# 04_Motors.net
KiCad netlist of a schematic drawn in Altium Designer
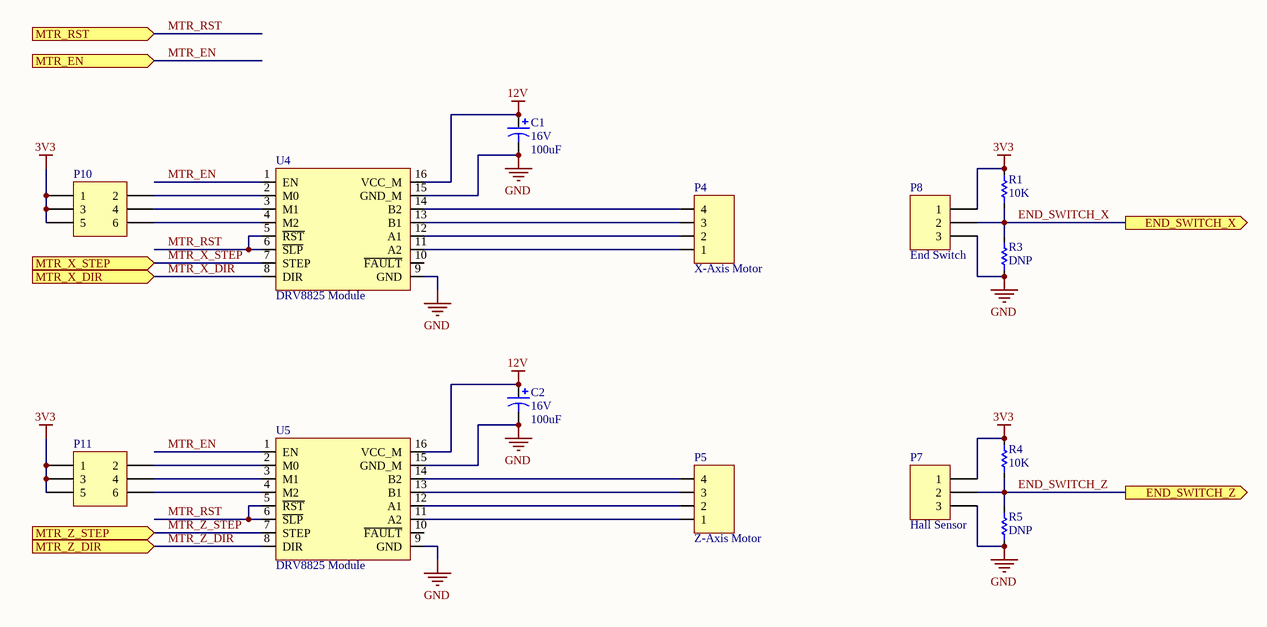
[diagram p0: 04_Motors.SchDoc]

(export (version "E")
  (design (tool "Eeschema 10.0.6"))
  (components
    (comp (ref "C1")
      (value "16V")
      (footprint "Moji Footprintovi:Electrolytic Cap 3.2mm")
      (description "Polarized Capacitor (Axial)")
      (fields
        (field (name "MANUFACTURER") "Würth Elektronik")
        (field (name "MANUFACTURER PART NUMBER") "870135675003")
        (field (name "ALTIUM_VALUE") "100uF")
      )
      (libsource (lib "Schematic_Misc") (part "Cap Electrolytic"))
    )
    (comp (ref "C2")
      (value "16V")
      (footprint "Moji Footprintovi:Electrolytic Cap 3.2mm")
      (description "Polarized Capacitor (Axial)")
      (fields
        (field (name "MANUFACTURER") "Würth Elektronik")
        (field (name "MANUFACTURER PART NUMBER") "870135675003")
        (field (name "ALTIUM_VALUE") "100uF")
      )
      (libsource (lib "Schematic_Misc") (part "Cap Electrolytic"))
    )
    (comp (ref "P4")
      (value "X-Axis Motor")
      (footprint "Footprint_Misc:TERMINAL_4POS_90DEG_2PART")
      (description "TERM BLOCK HDR 4POS 90DEG 3.5MM")
      (fields
        (field (name "DISTRIBUTOR PART NUMBER") "732-2771-ND")
        (field (name "MANUFACTURER") "Würth Elektronik")
      )
      (libsource (lib "Schematic_Misc") (part "Terminal 4_691322110004"))
    )
    (comp (ref "P5")
      (value "Z-Axis Motor")
      (footprint "Footprint_Misc:TERMINAL_4POS_90DEG_2PART")
      (description "TERM BLOCK HDR 4POS 90DEG 3.5MM")
      (fields
        (field (name "DISTRIBUTOR PART NUMBER") "732-2771-ND")
        (field (name "MANUFACTURER") "Würth Elektronik")
      )
      (libsource (lib "Schematic_Misc") (part "Terminal 4_691322110004"))
    )
    (comp (ref "P7")
      (value "Hall Sensor")
      (footprint "Footprint_Misc:TERMINAL_3POS_90DEG_2PART")
      (description "TERM BLOCK HDR 3POS 90DEG 3.5MM")
      (fields
        (field (name "MANUFACTURER") "Würth Elektronik")
        (field (name "MANUFACTURER PART NUMBER") "691322110003")
      )
      (libsource (lib "Schematic_Misc") (part "Terminal 3_691322110003_1"))
    )
    (comp (ref "P8")
      (value "End Switch")
      (footprint "Footprint_Misc:TERMINAL_3POS_90DEG_2PART")
      (description "TERM BLOCK HDR 3POS 90DEG 3.5MM")
      (fields
        (field (name "MANUFACTURER") "Würth Elektronik")
        (field (name "MANUFACTURER PART NUMBER") "691322110003")
      )
      (libsource (lib "Schematic_Misc") (part "Terminal 3_691322110003_1"))
    )
    (comp (ref "P10")
      (value "Header 3X2")
      (footprint "HDR2X3")
      (description "Header, 3-Pin, Dual row")
      (fields (field (name "DISTRIBUTOR PART NUMBER") "WM13106-ND") (field (name "MANUFACTURER") "Molex"))
      (libsource (lib "Miscellaneous Connectors") (part "Header 3X2"))
    )
    (comp (ref "P11")
      (value "Header 3X2")
      (footprint "HDR2X3")
      (description "Header, 3-Pin, Dual row")
      (fields (field (name "DISTRIBUTOR PART NUMBER") "WM13106-ND") (field (name "MANUFACTURER") "Molex"))
      (libsource (lib "Miscellaneous Connectors") (part "Header 3X2"))
    )
    (comp (ref "R1")
      (value "10K")
      (footprint "Moji Footprintovi:0603")
      (description "Resistor")
      (fields
        (field (name "DISTRIBUTOR PART NUMBER") "13-AA0603FR-0710KLCT-ND")
        (field (name "MANUFACTURER") "YAGEO")
      )
      (libsource (lib "Schematic_Misc") (part "Res"))
    )
    (comp (ref "R3")
      (value "DNP")
      (footprint "Moji Footprintovi:0603")
      (description "Resistor")
      (fields
        (field (name "DISTRIBUTOR PART NUMBER") "13-AA0603FR-0710KLCT-ND")
        (field (name "MANUFACTURER") "YAGEO")
      )
      (libsource (lib "Schematic_Misc") (part "Res"))
    )
    (comp (ref "R4")
      (value "10K")
      (footprint "Moji Footprintovi:0603")
      (description "Resistor")
      (fields
        (field (name "DISTRIBUTOR PART NUMBER") "13-AA0603FR-0710KLCT-ND")
        (field (name "MANUFACTURER") "YAGEO")
      )
      (libsource (lib "Schematic_Misc") (part "Res"))
    )
    (comp (ref "R5")
      (value "DNP")
      (footprint "Moji Footprintovi:0603")
      (description "Resistor")
      (fields
        (field (name "DISTRIBUTOR PART NUMBER") "13-AA0603FR-0710KLCT-ND")
        (field (name "MANUFACTURER") "YAGEO")
      )
      (libsource (lib "Schematic_Misc") (part "Res"))
    )
    (comp (ref "U4")
      (value "DRV8825 Module")
      (footprint "Footprint_Misc:DRV8825_Module")
      (fields (field (name "DISTRIBUTOR PART NUMBER") "https://www.aliexpress.com/item/32597532420.html"))
      (libsource (lib "Schematic_Misc") (part "DRV8825 Module"))
    )
    (comp (ref "U5")
      (value "DRV8825 Module")
      (footprint "Footprint_Misc:DRV8825_Module")
      (fields (field (name "DISTRIBUTOR PART NUMBER") "https://www.aliexpress.com/item/32597532420.html"))
      (libsource (lib "Schematic_Misc") (part "DRV8825 Module"))
    )
  )
  (nets
    (net (code "1") (name "/END_SWITCH_X") (class "Default")
      (node (ref "P8") (pin "2") (pinfunction "2_2") (pintype "passive"))
      (node (ref "R1") (pin "1") (pinfunction "1_1") (pintype "passive"))
      (node (ref "R3") (pin "2") (pinfunction "2_2") (pintype "passive"))
    )
    (net (code "2") (name "/END_SWITCH_Z") (class "Default")
      (node (ref "P7") (pin "2") (pinfunction "2_2") (pintype "passive"))
      (node (ref "R4") (pin "1") (pinfunction "1_1") (pintype "passive"))
      (node (ref "R5") (pin "2") (pinfunction "2_2") (pintype "passive"))
    )
    (net (code "3") (name "/MTR_EN") (class "Default")
      (node (ref "U4") (pin "1") (pinfunction "EN_1") (pintype "passive"))
      (node (ref "U5") (pin "1") (pinfunction "EN_1") (pintype "passive"))
    )
    (net (code "4") (name "/MTR_RST") (class "Default")
      (node (ref "U4") (pin "5") (pinfunction "~{RST}_5") (pintype "passive"))
      (node (ref "U4") (pin "6") (pinfunction "~{SLP}_6") (pintype "passive"))
      (node (ref "U5") (pin "5") (pinfunction "~{RST}_5") (pintype "passive"))
      (node (ref "U5") (pin "6") (pinfunction "~{SLP}_6") (pintype "passive"))
    )
    (net (code "5") (name "/MTR_X_DIR") (class "Default")
      (node (ref "U4") (pin "8") (pinfunction "DIR_8") (pintype "passive"))
    )
    (net (code "6") (name "/MTR_X_STEP") (class "Default")
      (node (ref "U4") (pin "7") (pinfunction "STEP_7") (pintype "passive"))
    )
    (net (code "7") (name "/MTR_Z_DIR") (class "Default")
      (node (ref "U5") (pin "8") (pinfunction "DIR_8") (pintype "passive"))
    )
    (net (code "8") (name "/MTR_Z_STEP") (class "Default")
      (node (ref "U5") (pin "7") (pinfunction "STEP_7") (pintype "passive"))
    )
    (net (code "9") (name "3V3") (class "Default")
      (node (ref "P10") (pin "1") (pinfunction "1_1") (pintype "passive"))
      (node (ref "P10") (pin "3") (pinfunction "3_3") (pintype "passive"))
      (node (ref "P10") (pin "5") (pinfunction "5_5") (pintype "passive"))
      (node (ref "P11") (pin "1") (pinfunction "1_1") (pintype "passive"))
      (node (ref "P11") (pin "3") (pinfunction "3_3") (pintype "passive"))
      (node (ref "P11") (pin "5") (pinfunction "5_5") (pintype "passive"))
      (node (ref "P7") (pin "1") (pinfunction "1_1") (pintype "passive"))
      (node (ref "P8") (pin "1") (pinfunction "1_1") (pintype "passive"))
      (node (ref "R1") (pin "2") (pinfunction "2_2") (pintype "passive"))
      (node (ref "R4") (pin "2") (pinfunction "2_2") (pintype "passive"))
    )
    (net (code "10") (name "12V") (class "Default")
      (node (ref "C1") (pin "1") (pinfunction "1_1") (pintype "passive"))
      (node (ref "C2") (pin "1") (pinfunction "1_1") (pintype "passive"))
      (node (ref "U4") (pin "16") (pinfunction "VCC_M_16") (pintype "passive"))
      (node (ref "U5") (pin "16") (pinfunction "VCC_M_16") (pintype "passive"))
    )
    (net (code "11") (name "GND") (class "Default")
      (node (ref "C1") (pin "2") (pinfunction "2_2") (pintype "passive"))
      (node (ref "C2") (pin "2") (pinfunction "2_2") (pintype "passive"))
      (node (ref "P7") (pin "3") (pinfunction "3_3") (pintype "passive"))
      (node (ref "P8") (pin "3") (pinfunction "3_3") (pintype "passive"))
      (node (ref "R3") (pin "1") (pinfunction "1_1") (pintype "passive"))
      (node (ref "R5") (pin "1") (pinfunction "1_1") (pintype "passive"))
      (node (ref "U4") (pin "15") (pinfunction "GND_M_15") (pintype "passive"))
      (node (ref "U4") (pin "9") (pinfunction "GND_9") (pintype "passive"))
      (node (ref "U5") (pin "15") (pinfunction "GND_M_15") (pintype "passive"))
      (node (ref "U5") (pin "9") (pinfunction "GND_9") (pintype "passive"))
    )
    (net (code "12") (name "Net-(U4-A1)") (class "Default")
      (node (ref "P4") (pin "2") (pinfunction "2_2") (pintype "passive"))
      (node (ref "U4") (pin "12") (pinfunction "A1_12") (pintype "passive"))
    )
    (net (code "13") (name "Net-(U4-A2)") (class "Default")
      (node (ref "P4") (pin "1") (pinfunction "1_1") (pintype "passive"))
      (node (ref "U4") (pin "11") (pinfunction "A2_11") (pintype "passive"))
    )
    (net (code "14") (name "Net-(U4-B1)") (class "Default")
      (node (ref "P4") (pin "3") (pinfunction "3_3") (pintype "passive"))
      (node (ref "U4") (pin "13") (pinfunction "B1_13") (pintype "passive"))
    )
    (net (code "15") (name "Net-(U4-B2)") (class "Default")
      (node (ref "P4") (pin "4") (pinfunction "4_4") (pintype "passive"))
      (node (ref "U4") (pin "14") (pinfunction "B2_14") (pintype "passive"))
    )
    (net (code "16") (name "Net-(U4-M0)") (class "Default")
      (node (ref "P10") (pin "2") (pinfunction "2_2") (pintype "passive"))
      (node (ref "U4") (pin "2") (pinfunction "M0_2") (pintype "passive"))
    )
    (net (code "17") (name "Net-(U4-M1)") (class "Default")
      (node (ref "P10") (pin "4") (pinfunction "4_4") (pintype "passive"))
      (node (ref "U4") (pin "3") (pinfunction "M1_3") (pintype "passive"))
    )
    (net (code "18") (name "Net-(U4-M2)") (class "Default")
      (node (ref "P10") (pin "6") (pinfunction "6_6") (pintype "passive"))
      (node (ref "U4") (pin "4") (pinfunction "M2_4") (pintype "passive"))
    )
    (net (code "19") (name "Net-(U5-A1)") (class "Default")
      (node (ref "P5") (pin "2") (pinfunction "2_2") (pintype "passive"))
      (node (ref "U5") (pin "12") (pinfunction "A1_12") (pintype "passive"))
    )
    (net (code "20") (name "Net-(U5-A2)") (class "Default")
      (node (ref "P5") (pin "1") (pinfunction "1_1") (pintype "passive"))
      (node (ref "U5") (pin "11") (pinfunction "A2_11") (pintype "passive"))
    )
    (net (code "21") (name "Net-(U5-B1)") (class "Default")
      (node (ref "P5") (pin "3") (pinfunction "3_3") (pintype "passive"))
      (node (ref "U5") (pin "13") (pinfunction "B1_13") (pintype "passive"))
    )
    (net (code "22") (name "Net-(U5-B2)") (class "Default")
      (node (ref "P5") (pin "4") (pinfunction "4_4") (pintype "passive"))
      (node (ref "U5") (pin "14") (pinfunction "B2_14") (pintype "passive"))
    )
    (net (code "23") (name "Net-(U5-M0)") (class "Default")
      (node (ref "P11") (pin "2") (pinfunction "2_2") (pintype "passive"))
      (node (ref "U5") (pin "2") (pinfunction "M0_2") (pintype "passive"))
    )
    (net (code "24") (name "Net-(U5-M1)") (class "Default")
      (node (ref "P11") (pin "4") (pinfunction "4_4") (pintype "passive"))
      (node (ref "U5") (pin "3") (pinfunction "M1_3") (pintype "passive"))
    )
    (net (code "25") (name "Net-(U5-M2)") (class "Default")
      (node (ref "P11") (pin "6") (pinfunction "6_6") (pintype "passive"))
      (node (ref "U5") (pin "4") (pinfunction "M2_4") (pintype "passive"))
    )
    (net (code "26") (name "unconnected-(U4-~{FAULT}-Pad10)") (class "Default")
      (node (ref "U4") (pin "10") (pinfunction "~{FAULT}_10") (pintype "passive"))
    )
    (net (code "27") (name "unconnected-(U5-~{FAULT}-Pad10)") (class "Default")
      (node (ref "U5") (pin "10") (pinfunction "~{FAULT}_10") (pintype "passive"))
    )
  )
)
